# Mechanical.net
KiCad netlist of a schematic drawn in Altium Designer
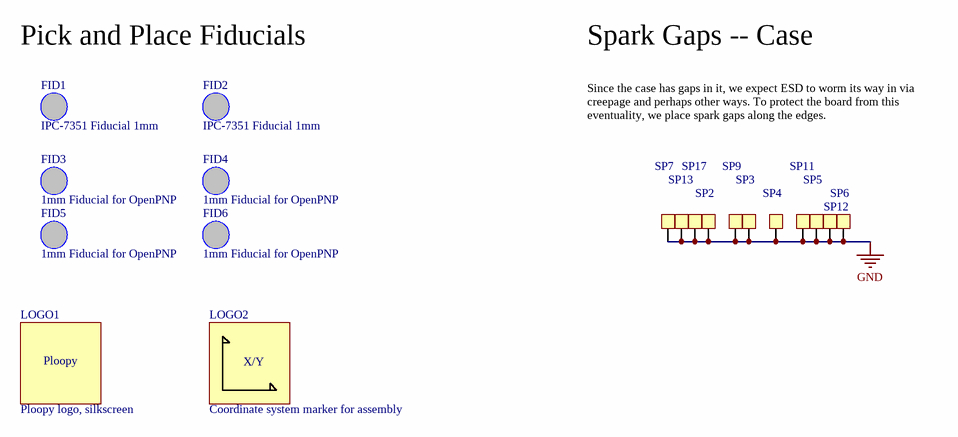
[diagram p0: Mechanical.SchDoc]

(export (version "E")
  (design (tool "Eeschema 10.0.6"))
  (components
    (comp (ref "FID1")
      (value "IPC-7351 Fiducial 1mm")
      (footprint "FIDUCIAL_1.5")
      (libsource (lib "Mechanical") (part "FIDUCIAL_1.5"))
    )
    (comp (ref "FID2")
      (value "IPC-7351 Fiducial 1mm")
      (footprint "FIDUCIAL_1.5")
      (libsource (lib "Mechanical") (part "FIDUCIAL_1.5"))
    )
    (comp (ref "FID3")
      (value "1mm Fiducial for OpenPNP")
      (footprint "FIDUCIAL-NEW")
      (libsource (lib "Mechanical") (part "FIDUCIAL_NEW"))
    )
    (comp (ref "FID4")
      (value "1mm Fiducial for OpenPNP")
      (footprint "FIDUCIAL-NEW")
      (libsource (lib "Mechanical") (part "FIDUCIAL_NEW"))
    )
    (comp (ref "FID5")
      (value "1mm Fiducial for OpenPNP")
      (footprint "FIDUCIAL-NEW")
      (libsource (lib "Mechanical") (part "FIDUCIAL_NEW"))
    )
    (comp (ref "FID6")
      (value "1mm Fiducial for OpenPNP")
      (footprint "FIDUCIAL-NEW")
      (libsource (lib "Mechanical") (part "FIDUCIAL_NEW"))
    )
    (comp (ref "LOGO1")
      (value "Ploopy logo, silkscreen")
      (footprint "PloopyLogo")
      (libsource (lib "Graphics") (part "PloopyLogo"))
    )
    (comp (ref "LOGO2")
      (value "Coordinate system marker for assembly")
      (footprint "Coordinate System")
      (libsource (lib "Graphics") (part "CoordinateSystem"))
    )
    (comp (ref "SP2")
      (value "Spark Gap")
      (footprint "SparkGap")
      (description "Open square pad for spark gapping")
      (libsource (lib "PCBFeatures") (part "Spark Gap"))
    )
    (comp (ref "SP3")
      (value "Spark Gap")
      (footprint "SparkGap")
      (description "Open square pad for spark gapping")
      (libsource (lib "PCBFeatures") (part "Spark Gap"))
    )
    (comp (ref "SP4")
      (value "Spark Gap")
      (footprint "SparkGap")
      (description "Open square pad for spark gapping")
      (libsource (lib "PCBFeatures") (part "Spark Gap"))
    )
    (comp (ref "SP5")
      (value "Spark Gap")
      (footprint "SparkGap")
      (description "Open square pad for spark gapping")
      (libsource (lib "PCBFeatures") (part "Spark Gap"))
    )
    (comp (ref "SP6")
      (value "Spark Gap")
      (footprint "SparkGap")
      (description "Open square pad for spark gapping")
      (libsource (lib "PCBFeatures") (part "Spark Gap"))
    )
    (comp (ref "SP7")
      (value "Spark Gap")
      (footprint "SparkGap")
      (description "Open square pad for spark gapping")
      (libsource (lib "PCBFeatures") (part "Spark Gap"))
    )
    (comp (ref "SP9")
      (value "Spark Gap")
      (footprint "SparkGap")
      (description "Open square pad for spark gapping")
      (libsource (lib "PCBFeatures") (part "Spark Gap"))
    )
    (comp (ref "SP11")
      (value "Spark Gap")
      (footprint "SparkGap")
      (description "Open square pad for spark gapping")
      (libsource (lib "PCBFeatures") (part "Spark Gap"))
    )
    (comp (ref "SP12")
      (value "Spark Gap")
      (footprint "SparkGap")
      (description "Open square pad for spark gapping")
      (libsource (lib "PCBFeatures") (part "Spark Gap"))
    )
    (comp (ref "SP13")
      (value "Spark Gap")
      (footprint "SparkGap")
      (description "Open square pad for spark gapping")
      (libsource (lib "PCBFeatures") (part "Spark Gap"))
    )
    (comp (ref "SP17")
      (value "Spark Gap")
      (footprint "SparkGap")
      (description "Open square pad for spark gapping")
      (libsource (lib "PCBFeatures") (part "Spark Gap"))
    )
  )
  (nets
    (net (code "1") (name "GND") (class "Default")
      (node (ref "SP11") (pin "1") (pinfunction "1_1") (pintype "passive"))
      (node (ref "SP12") (pin "1") (pinfunction "1_1") (pintype "passive"))
      (node (ref "SP13") (pin "1") (pinfunction "1_1") (pintype "passive"))
      (node (ref "SP17") (pin "1") (pinfunction "1_1") (pintype "passive"))
      (node (ref "SP2") (pin "1") (pinfunction "1_1") (pintype "passive"))
      (node (ref "SP3") (pin "1") (pinfunction "1_1") (pintype "passive"))
      (node (ref "SP4") (pin "1") (pinfunction "1_1") (pintype "passive"))
      (node (ref "SP5") (pin "1") (pinfunction "1_1") (pintype "passive"))
      (node (ref "SP6") (pin "1") (pinfunction "1_1") (pintype "passive"))
      (node (ref "SP7") (pin "1") (pinfunction "1_1") (pintype "passive"))
      (node (ref "SP9") (pin "1") (pinfunction "1_1") (pintype "passive"))
    )
    (net (code "2") (name "unconnected-(FID1-Pad1)") (class "Default")
      (node (ref "FID1") (pin "1") (pinfunction "1_1") (pintype "passive"))
    )
    (net (code "3") (name "unconnected-(FID2-Pad1)") (class "Default")
      (node (ref "FID2") (pin "1") (pinfunction "1_1") (pintype "passive"))
    )
    (net (code "4") (name "unconnected-(FID3-Pad1)") (class "Default")
      (node (ref "FID3") (pin "1") (pinfunction "1_1") (pintype "passive"))
    )
    (net (code "5") (name "unconnected-(FID4-Pad1)") (class "Default")
      (node (ref "FID4") (pin "1") (pinfunction "1_1") (pintype "passive"))
    )
    (net (code "6") (name "unconnected-(FID5-Pad1)") (class "Default")
      (node (ref "FID5") (pin "1") (pinfunction "1_1") (pintype "passive"))
    )
    (net (code "7") (name "unconnected-(FID6-Pad1)") (class "Default")
      (node (ref "FID6") (pin "1") (pinfunction "1_1") (pintype "passive"))
    )
  )
)
